# nes_snes_4_port.net
KiCad netlist of a schematic drawn in EAGLE
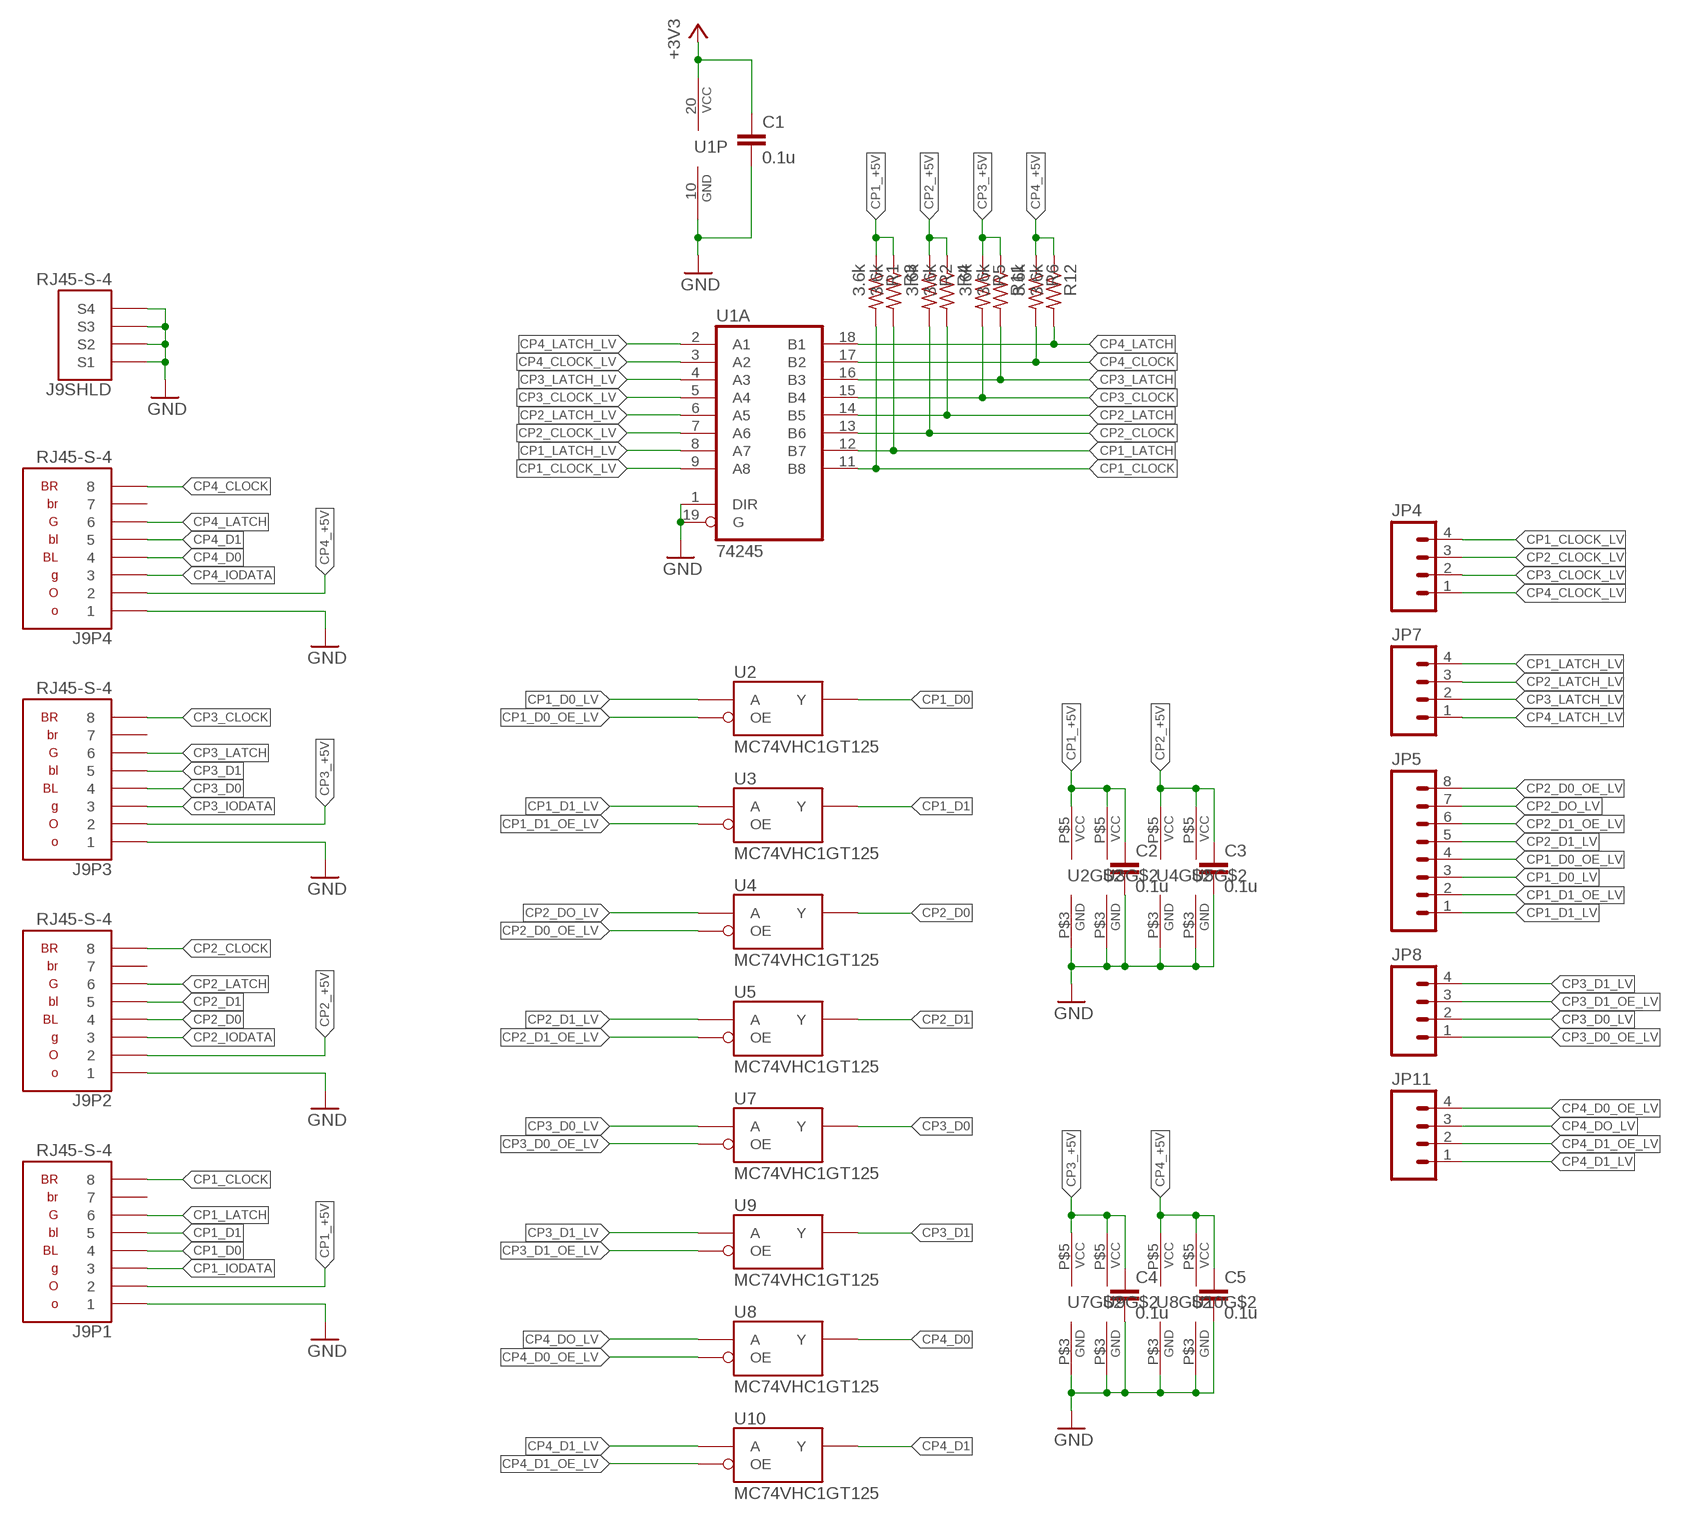
[diagram p0: schematic, sheet 1, part 1 of 2]
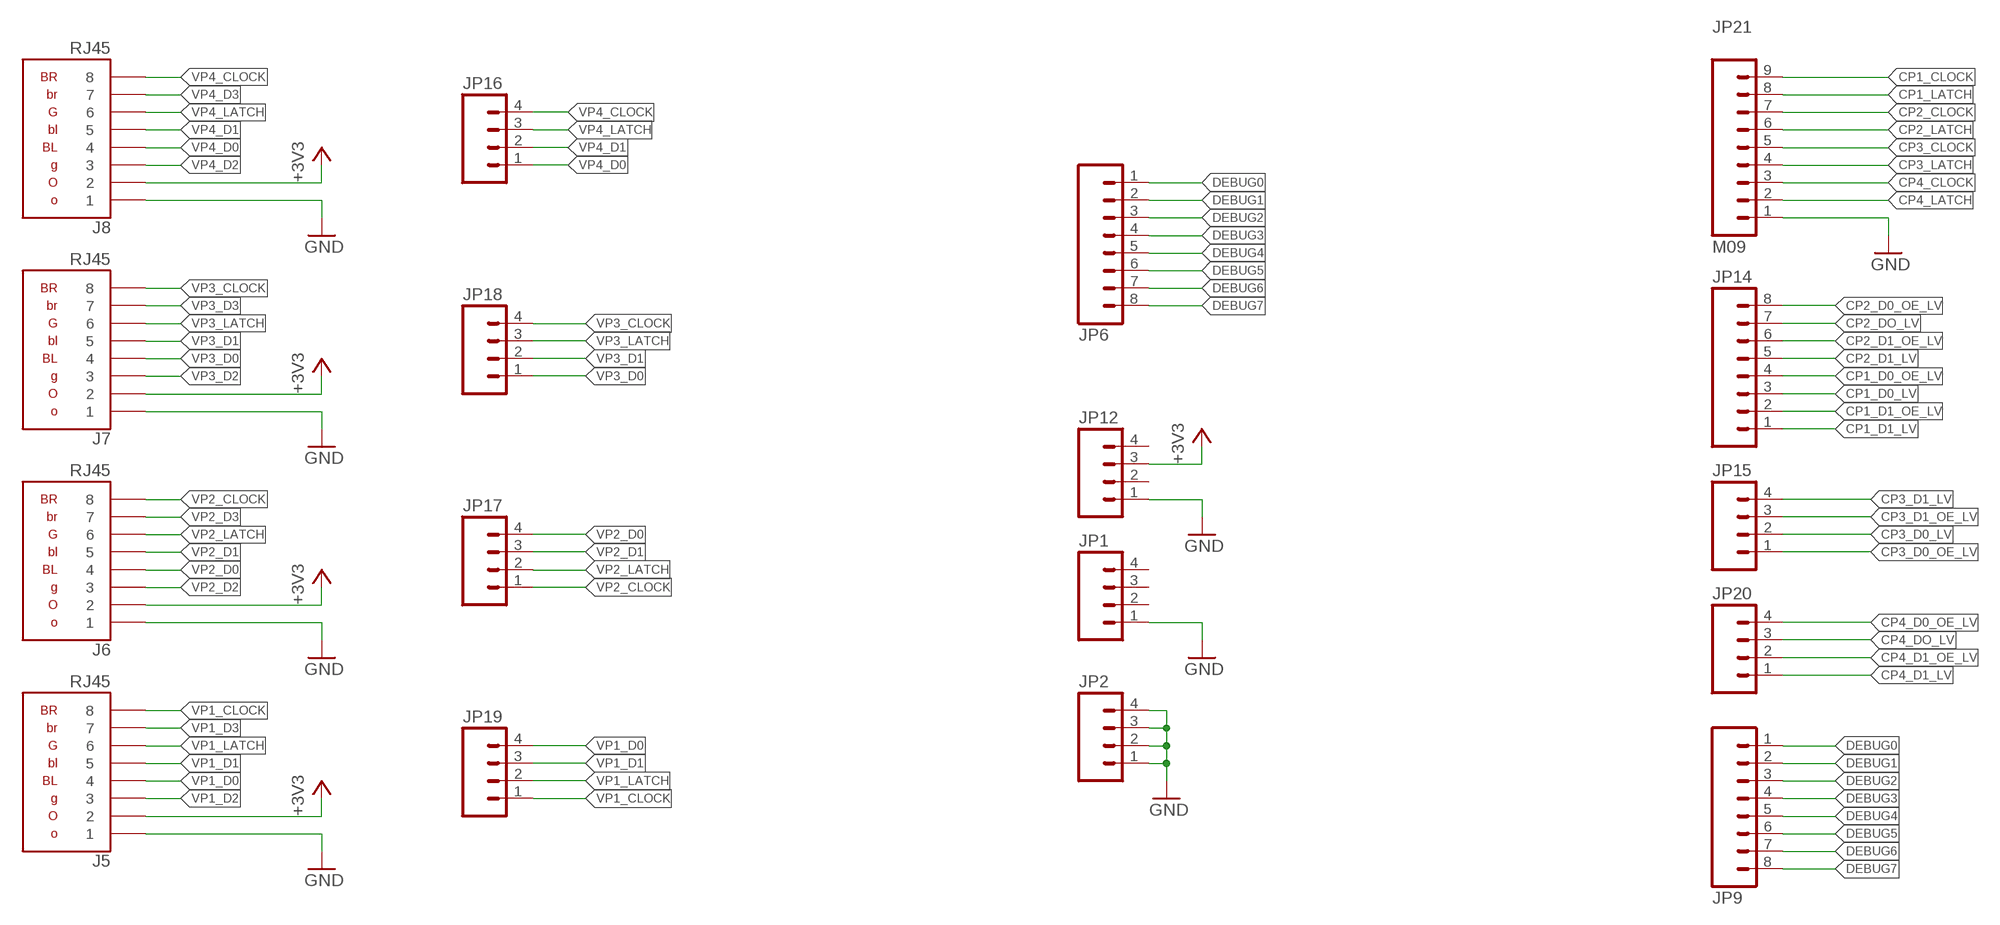
[diagram p1: schematic, sheet 1, part 2 of 2]

(export (version "E")
  (design (tool "Eeschema 10.0.6"))
  (components
    (comp (ref "C1")
      (value "0.1u")
      (footprint "eagle-import:C0603")
      (libsource (lib "eagle-import") (part "C-EUC0603"))
    )
    (comp (ref "C2")
      (value "0.1u")
      (footprint "eagle-import:C0603")
      (libsource (lib "eagle-import") (part "C-EUC0603"))
    )
    (comp (ref "C3")
      (value "0.1u")
      (footprint "eagle-import:C0603")
      (libsource (lib "eagle-import") (part "C-EUC0603"))
    )
    (comp (ref "C4")
      (value "0.1u")
      (footprint "eagle-import:C0603")
      (libsource (lib "eagle-import") (part "C-EUC0603"))
    )
    (comp (ref "C5")
      (value "0.1u")
      (footprint "eagle-import:C0603")
      (libsource (lib "eagle-import") (part "C-EUC0603"))
    )
    (comp (ref "J5")
      (value "RJ45")
      (footprint "eagle-import:RJ45")
      (libsource (lib "eagle-import") (part "RJ45"))
    )
    (comp (ref "J6")
      (value "RJ45")
      (footprint "eagle-import:RJ45")
      (libsource (lib "eagle-import") (part "RJ45"))
    )
    (comp (ref "J7")
      (value "RJ45")
      (footprint "eagle-import:RJ45")
      (libsource (lib "eagle-import") (part "RJ45"))
    )
    (comp (ref "J8")
      (value "RJ45")
      (footprint "eagle-import:RJ45")
      (libsource (lib "eagle-import") (part "RJ45"))
    )
    (comp (ref "J9")
      (value "RJ45-S-4")
      (footprint "eagle-import:RJ45-S-4")
      (libsource (lib "eagle-import") (part "RJ45-S-4"))
    )
    (comp (ref "JP1")
      (value "M04PTH")
      (footprint "eagle-import:1X04")
      (libsource (lib "eagle-import") (part "M04PTH"))
    )
    (comp (ref "JP2")
      (value "M04PTH")
      (footprint "eagle-import:1X04")
      (libsource (lib "eagle-import") (part "M04PTH"))
    )
    (comp (ref "JP4")
      (value "M04PTH")
      (footprint "eagle-import:1X04")
      (libsource (lib "eagle-import") (part "M04PTH"))
    )
    (comp (ref "JP5")
      (value "M081X08")
      (footprint "eagle-import:1X08")
      (libsource (lib "eagle-import") (part "M081X08"))
    )
    (comp (ref "JP6")
      (value "M081X08")
      (footprint "eagle-import:1X08")
      (libsource (lib "eagle-import") (part "M081X08"))
    )
    (comp (ref "JP7")
      (value "M04PTH")
      (footprint "eagle-import:1X04")
      (libsource (lib "eagle-import") (part "M04PTH"))
    )
    (comp (ref "JP8")
      (value "M04PTH")
      (footprint "eagle-import:1X04")
      (libsource (lib "eagle-import") (part "M04PTH"))
    )
    (comp (ref "JP9")
      (value "M081X08")
      (footprint "eagle-import:1X08")
      (libsource (lib "eagle-import") (part "M081X08"))
    )
    (comp (ref "JP11")
      (value "M04PTH")
      (footprint "eagle-import:1X04")
      (libsource (lib "eagle-import") (part "M04PTH"))
    )
    (comp (ref "JP12")
      (value "M04PTH")
      (footprint "eagle-import:1X04")
      (libsource (lib "eagle-import") (part "M04PTH"))
    )
    (comp (ref "JP14")
      (value "M081X08")
      (footprint "eagle-import:1X08")
      (libsource (lib "eagle-import") (part "M081X08"))
    )
    (comp (ref "JP15")
      (value "M04PTH")
      (footprint "eagle-import:1X04")
      (libsource (lib "eagle-import") (part "M04PTH"))
    )
    (comp (ref "JP16")
      (value "M04PTH")
      (footprint "eagle-import:1X04")
      (libsource (lib "eagle-import") (part "M04PTH"))
    )
    (comp (ref "JP17")
      (value "M04PTH")
      (footprint "eagle-import:1X04")
      (libsource (lib "eagle-import") (part "M04PTH"))
    )
    (comp (ref "JP18")
      (value "M04PTH")
      (footprint "eagle-import:1X04")
      (libsource (lib "eagle-import") (part "M04PTH"))
    )
    (comp (ref "JP19")
      (value "M04PTH")
      (footprint "eagle-import:1X04")
      (libsource (lib "eagle-import") (part "M04PTH"))
    )
    (comp (ref "JP20")
      (value "M04PTH")
      (footprint "eagle-import:1X04")
      (libsource (lib "eagle-import") (part "M04PTH"))
    )
    (comp (ref "JP21")
      (value "M09")
      (footprint "eagle-import:1X09")
      (libsource (lib "eagle-import") (part "M09"))
    )
    (comp (ref "R1")
      (value "3.6k")
      (footprint "eagle-import:0207_2V")
      (libsource (lib "eagle-import") (part "R-US_0207/2V"))
    )
    (comp (ref "R2")
      (value "3.6k")
      (footprint "eagle-import:0207_2V")
      (libsource (lib "eagle-import") (part "R-US_0207/2V"))
    )
    (comp (ref "R3")
      (value "3.6k")
      (footprint "eagle-import:0207_2V")
      (libsource (lib "eagle-import") (part "R-US_0207/2V"))
    )
    (comp (ref "R4")
      (value "3.6k")
      (footprint "eagle-import:0207_2V")
      (libsource (lib "eagle-import") (part "R-US_0207/2V"))
    )
    (comp (ref "R5")
      (value "3.6k")
      (footprint "eagle-import:0207_2V")
      (libsource (lib "eagle-import") (part "R-US_0207/2V"))
    )
    (comp (ref "R6")
      (value "3.6k")
      (footprint "eagle-import:0207_2V")
      (libsource (lib "eagle-import") (part "R-US_0207/2V"))
    )
    (comp (ref "R11")
      (value "3.6k")
      (footprint "eagle-import:0207_2V")
      (libsource (lib "eagle-import") (part "R-US_0207/2V"))
    )
    (comp (ref "R12")
      (value "3.6k")
      (footprint "eagle-import:0207_2V")
      (libsource (lib "eagle-import") (part "R-US_0207/2V"))
    )
    (comp (ref "U1")
      (value "74245")
      (footprint "eagle-import:DIL20")
      (libsource (lib "eagle-import") (part "74245"))
    )
    (comp (ref "U2")
      (value "MC74VHC1GT125")
      (footprint "eagle-import:TSOP-5")
      (libsource (lib "eagle-import") (part "MC74VHC1GT125"))
    )
    (comp (ref "U3")
      (value "MC74VHC1GT125")
      (footprint "eagle-import:TSOP-5")
      (libsource (lib "eagle-import") (part "MC74VHC1GT125"))
    )
    (comp (ref "U4")
      (value "MC74VHC1GT125")
      (footprint "eagle-import:TSOP-5")
      (libsource (lib "eagle-import") (part "MC74VHC1GT125"))
    )
    (comp (ref "U5")
      (value "MC74VHC1GT125")
      (footprint "eagle-import:TSOP-5")
      (libsource (lib "eagle-import") (part "MC74VHC1GT125"))
    )
    (comp (ref "U7")
      (value "MC74VHC1GT125")
      (footprint "eagle-import:TSOP-5")
      (libsource (lib "eagle-import") (part "MC74VHC1GT125"))
    )
    (comp (ref "U8")
      (value "MC74VHC1GT125")
      (footprint "eagle-import:TSOP-5")
      (libsource (lib "eagle-import") (part "MC74VHC1GT125"))
    )
    (comp (ref "U9")
      (value "MC74VHC1GT125")
      (footprint "eagle-import:TSOP-5")
      (libsource (lib "eagle-import") (part "MC74VHC1GT125"))
    )
    (comp (ref "U10")
      (value "MC74VHC1GT125")
      (footprint "eagle-import:TSOP-5")
      (libsource (lib "eagle-import") (part "MC74VHC1GT125"))
    )
  )
  (nets
    (net (code "1") (name "+3V3") (class "Default")
      (node (ref "C1") (pin "1") (pinfunction "1_1") (pintype "passive"))
      (node (ref "J5") (pin "2") (pinfunction "2_2") (pintype "bidirectional"))
      (node (ref "J6") (pin "2") (pinfunction "2_2") (pintype "bidirectional"))
      (node (ref "J7") (pin "2") (pinfunction "2_2") (pintype "bidirectional"))
      (node (ref "J8") (pin "2") (pinfunction "2_2") (pintype "bidirectional"))
      (node (ref "JP12") (pin "3") (pinfunction "3_3") (pintype "passive"))
      (node (ref "U1") (pin "20") (pinfunction "VCC_20") (pintype "power_in"))
    )
    (net (code "2") (name "CP1_+5V") (class "Default")
      (node (ref "C2") (pin "1") (pinfunction "1_1") (pintype "passive"))
      (node (ref "J9") (pin "1-2") (pinfunction "2_1-2") (pintype "bidirectional"))
      (node (ref "R1") (pin "1") (pinfunction "1_1") (pintype "passive"))
      (node (ref "R3") (pin "1") (pinfunction "1_1") (pintype "passive"))
      (node (ref "U2") (pin "P$5") (pinfunction "VCC_P$5") (pintype "power_in"))
      (node (ref "U3") (pin "P$5") (pinfunction "VCC_P$5") (pintype "power_in"))
    )
    (net (code "3") (name "CP1_CLOCK") (class "Default")
      (node (ref "J9") (pin "1-8") (pinfunction "8_1-8") (pintype "bidirectional"))
      (node (ref "JP21") (pin "9") (pinfunction "9_9") (pintype "passive"))
      (node (ref "R1") (pin "2") (pinfunction "2_2") (pintype "passive"))
      (node (ref "U1") (pin "11") (pinfunction "B8_11") (pintype "bidirectional"))
    )
    (net (code "4") (name "CP1_CLOCK_LV") (class "Default")
      (node (ref "JP4") (pin "4") (pinfunction "4_4") (pintype "passive"))
      (node (ref "U1") (pin "9") (pinfunction "A8_9") (pintype "bidirectional"))
    )
    (net (code "5") (name "CP1_D0") (class "Default")
      (node (ref "J9") (pin "1-4") (pinfunction "4_1-4") (pintype "bidirectional"))
      (node (ref "U2") (pin "P$4") (pinfunction "Y_P$4") (pintype "bidirectional"))
    )
    (net (code "6") (name "CP1_D0_LV") (class "Default")
      (node (ref "JP14") (pin "3") (pinfunction "3_3") (pintype "passive"))
      (node (ref "JP5") (pin "3") (pinfunction "3_3") (pintype "passive"))
      (node (ref "U2") (pin "P$2") (pinfunction "A_P$2") (pintype "bidirectional"))
    )
    (net (code "7") (name "CP1_D0_OE_LV") (class "Default")
      (node (ref "JP14") (pin "4") (pinfunction "4_4") (pintype "passive"))
      (node (ref "JP5") (pin "4") (pinfunction "4_4") (pintype "passive"))
      (node (ref "U2") (pin "P$1") (pinfunction "OE_P$1") (pintype "bidirectional"))
    )
    (net (code "8") (name "CP1_D1") (class "Default")
      (node (ref "J9") (pin "1-5") (pinfunction "5_1-5") (pintype "bidirectional"))
      (node (ref "U3") (pin "P$4") (pinfunction "Y_P$4") (pintype "bidirectional"))
    )
    (net (code "9") (name "CP1_D1_LV") (class "Default")
      (node (ref "JP14") (pin "1") (pinfunction "1_1") (pintype "passive"))
      (node (ref "JP5") (pin "1") (pinfunction "1_1") (pintype "passive"))
      (node (ref "U3") (pin "P$2") (pinfunction "A_P$2") (pintype "bidirectional"))
    )
    (net (code "10") (name "CP1_D1_OE_LV") (class "Default")
      (node (ref "JP14") (pin "2") (pinfunction "2_2") (pintype "passive"))
      (node (ref "JP5") (pin "2") (pinfunction "2_2") (pintype "passive"))
      (node (ref "U3") (pin "P$1") (pinfunction "OE_P$1") (pintype "bidirectional"))
    )
    (net (code "11") (name "CP1_IODATA") (class "Default")
      (node (ref "J9") (pin "1-3") (pinfunction "3_1-3") (pintype "bidirectional"))
    )
    (net (code "12") (name "CP1_LATCH") (class "Default")
      (node (ref "J9") (pin "1-6") (pinfunction "6_1-6") (pintype "bidirectional"))
      (node (ref "JP21") (pin "8") (pinfunction "8_8") (pintype "passive"))
      (node (ref "R3") (pin "2") (pinfunction "2_2") (pintype "passive"))
      (node (ref "U1") (pin "12") (pinfunction "B7_12") (pintype "bidirectional"))
    )
    (net (code "13") (name "CP1_LATCH_LV") (class "Default")
      (node (ref "JP7") (pin "4") (pinfunction "4_4") (pintype "passive"))
      (node (ref "U1") (pin "8") (pinfunction "A7_8") (pintype "bidirectional"))
    )
    (net (code "14") (name "CP2_+5V") (class "Default")
      (node (ref "C3") (pin "1") (pinfunction "1_1") (pintype "passive"))
      (node (ref "J9") (pin "2-2") (pinfunction "2_2-2") (pintype "bidirectional"))
      (node (ref "R2") (pin "1") (pinfunction "1_1") (pintype "passive"))
      (node (ref "R4") (pin "1") (pinfunction "1_1") (pintype "passive"))
      (node (ref "U4") (pin "P$5") (pinfunction "VCC_P$5") (pintype "power_in"))
      (node (ref "U5") (pin "P$5") (pinfunction "VCC_P$5") (pintype "power_in"))
    )
    (net (code "15") (name "CP2_CLOCK") (class "Default")
      (node (ref "J9") (pin "2-8") (pinfunction "8_2-8") (pintype "bidirectional"))
      (node (ref "JP21") (pin "7") (pinfunction "7_7") (pintype "passive"))
      (node (ref "R2") (pin "2") (pinfunction "2_2") (pintype "passive"))
      (node (ref "U1") (pin "13") (pinfunction "B6_13") (pintype "bidirectional"))
    )
    (net (code "16") (name "CP2_CLOCK_LV") (class "Default")
      (node (ref "JP4") (pin "3") (pinfunction "3_3") (pintype "passive"))
      (node (ref "U1") (pin "7") (pinfunction "A6_7") (pintype "bidirectional"))
    )
    (net (code "17") (name "CP2_D0") (class "Default")
      (node (ref "J9") (pin "2-4") (pinfunction "4_2-4") (pintype "bidirectional"))
      (node (ref "U4") (pin "P$4") (pinfunction "Y_P$4") (pintype "bidirectional"))
    )
    (net (code "18") (name "CP2_D0_OE_LV") (class "Default")
      (node (ref "JP14") (pin "8") (pinfunction "8_8") (pintype "passive"))
      (node (ref "JP5") (pin "8") (pinfunction "8_8") (pintype "passive"))
      (node (ref "U4") (pin "P$1") (pinfunction "OE_P$1") (pintype "bidirectional"))
    )
    (net (code "19") (name "CP2_D1") (class "Default")
      (node (ref "J9") (pin "2-5") (pinfunction "5_2-5") (pintype "bidirectional"))
      (node (ref "U5") (pin "P$4") (pinfunction "Y_P$4") (pintype "bidirectional"))
    )
    (net (code "20") (name "CP2_D1_LV") (class "Default")
      (node (ref "JP14") (pin "5") (pinfunction "5_5") (pintype "passive"))
      (node (ref "JP5") (pin "5") (pinfunction "5_5") (pintype "passive"))
      (node (ref "U5") (pin "P$2") (pinfunction "A_P$2") (pintype "bidirectional"))
    )
    (net (code "21") (name "CP2_D1_OE_LV") (class "Default")
      (node (ref "JP14") (pin "6") (pinfunction "6_6") (pintype "passive"))
      (node (ref "JP5") (pin "6") (pinfunction "6_6") (pintype "passive"))
      (node (ref "U5") (pin "P$1") (pinfunction "OE_P$1") (pintype "bidirectional"))
    )
    (net (code "22") (name "CP2_DO_LV") (class "Default")
      (node (ref "JP14") (pin "7") (pinfunction "7_7") (pintype "passive"))
      (node (ref "JP5") (pin "7") (pinfunction "7_7") (pintype "passive"))
      (node (ref "U4") (pin "P$2") (pinfunction "A_P$2") (pintype "bidirectional"))
    )
    (net (code "23") (name "CP2_IODATA") (class "Default")
      (node (ref "J9") (pin "2-3") (pinfunction "3_2-3") (pintype "bidirectional"))
    )
    (net (code "24") (name "CP2_LATCH") (class "Default")
      (node (ref "J9") (pin "2-6") (pinfunction "6_2-6") (pintype "bidirectional"))
      (node (ref "JP21") (pin "6") (pinfunction "6_6") (pintype "passive"))
      (node (ref "R4") (pin "2") (pinfunction "2_2") (pintype "passive"))
      (node (ref "U1") (pin "14") (pinfunction "B5_14") (pintype "bidirectional"))
    )
    (net (code "25") (name "CP2_LATCH_LV") (class "Default")
      (node (ref "JP7") (pin "3") (pinfunction "3_3") (pintype "passive"))
      (node (ref "U1") (pin "6") (pinfunction "A5_6") (pintype "bidirectional"))
    )
    (net (code "26") (name "CP3_+5V") (class "Default")
      (node (ref "C4") (pin "1") (pinfunction "1_1") (pintype "passive"))
      (node (ref "J9") (pin "3-2") (pinfunction "2_3-2") (pintype "bidirectional"))
      (node (ref "R11") (pin "1") (pinfunction "1_1") (pintype "passive"))
      (node (ref "R5") (pin "1") (pinfunction "1_1") (pintype "passive"))
      (node (ref "U7") (pin "P$5") (pinfunction "VCC_P$5") (pintype "power_in"))
      (node (ref "U9") (pin "P$5") (pinfunction "VCC_P$5") (pintype "power_in"))
    )
    (net (code "27") (name "CP3_CLOCK") (class "Default")
      (node (ref "J9") (pin "3-8") (pinfunction "8_3-8") (pintype "bidirectional"))
      (node (ref "JP21") (pin "5") (pinfunction "5_5") (pintype "passive"))
      (node (ref "R5") (pin "2") (pinfunction "2_2") (pintype "passive"))
      (node (ref "U1") (pin "15") (pinfunction "B4_15") (pintype "bidirectional"))
    )
    (net (code "28") (name "CP3_CLOCK_LV") (class "Default")
      (node (ref "JP4") (pin "2") (pinfunction "2_2") (pintype "passive"))
      (node (ref "U1") (pin "5") (pinfunction "A4_5") (pintype "bidirectional"))
    )
    (net (code "29") (name "CP3_D0") (class "Default")
      (node (ref "J9") (pin "3-4") (pinfunction "4_3-4") (pintype "bidirectional"))
      (node (ref "U7") (pin "P$4") (pinfunction "Y_P$4") (pintype "bidirectional"))
    )
    (net (code "30") (name "CP3_D0_LV") (class "Default")
      (node (ref "JP15") (pin "2") (pinfunction "2_2") (pintype "passive"))
      (node (ref "JP8") (pin "2") (pinfunction "2_2") (pintype "passive"))
      (node (ref "U7") (pin "P$2") (pinfunction "A_P$2") (pintype "bidirectional"))
    )
    (net (code "31") (name "CP3_D0_OE_LV") (class "Default")
      (node (ref "JP15") (pin "1") (pinfunction "1_1") (pintype "passive"))
      (node (ref "JP8") (pin "1") (pinfunction "1_1") (pintype "passive"))
      (node (ref "U7") (pin "P$1") (pinfunction "OE_P$1") (pintype "bidirectional"))
    )
    (net (code "32") (name "CP3_D1") (class "Default")
      (node (ref "J9") (pin "3-5") (pinfunction "5_3-5") (pintype "bidirectional"))
      (node (ref "U9") (pin "P$4") (pinfunction "Y_P$4") (pintype "bidirectional"))
    )
    (net (code "33") (name "CP3_D1_LV") (class "Default")
      (node (ref "JP15") (pin "4") (pinfunction "4_4") (pintype "passive"))
      (node (ref "JP8") (pin "4") (pinfunction "4_4") (pintype "passive"))
      (node (ref "U9") (pin "P$2") (pinfunction "A_P$2") (pintype "bidirectional"))
    )
    (net (code "34") (name "CP3_D1_OE_LV") (class "Default")
      (node (ref "JP15") (pin "3") (pinfunction "3_3") (pintype "passive"))
      (node (ref "JP8") (pin "3") (pinfunction "3_3") (pintype "passive"))
      (node (ref "U9") (pin "P$1") (pinfunction "OE_P$1") (pintype "bidirectional"))
    )
    (net (code "35") (name "CP3_IODATA") (class "Default")
      (node (ref "J9") (pin "3-3") (pinfunction "3_3-3") (pintype "bidirectional"))
    )
    (net (code "36") (name "CP3_LATCH") (class "Default")
      (node (ref "J9") (pin "3-6") (pinfunction "6_3-6") (pintype "bidirectional"))
      (node (ref "JP21") (pin "4") (pinfunction "4_4") (pintype "passive"))
      (node (ref "R11") (pin "2") (pinfunction "2_2") (pintype "passive"))
      (node (ref "U1") (pin "16") (pinfunction "B3_16") (pintype "bidirectional"))
    )
    (net (code "37") (name "CP3_LATCH_LV") (class "Default")
      (node (ref "JP7") (pin "2") (pinfunction "2_2") (pintype "passive"))
      (node (ref "U1") (pin "4") (pinfunction "A3_4") (pintype "bidirectional"))
    )
    (net (code "38") (name "CP4_+5V") (class "Default")
      (node (ref "C5") (pin "1") (pinfunction "1_1") (pintype "passive"))
      (node (ref "J9") (pin "4-2") (pinfunction "2_4-2") (pintype "bidirectional"))
      (node (ref "R12") (pin "1") (pinfunction "1_1") (pintype "passive"))
      (node (ref "R6") (pin "1") (pinfunction "1_1") (pintype "passive"))
      (node (ref "U10") (pin "P$5") (pinfunction "VCC_P$5") (pintype "power_in"))
      (node (ref "U8") (pin "P$5") (pinfunction "VCC_P$5") (pintype "power_in"))
    )
    (net (code "39") (name "CP4_CLOCK") (class "Default")
      (node (ref "J9") (pin "4-8") (pinfunction "8_4-8") (pintype "bidirectional"))
      (node (ref "JP21") (pin "3") (pinfunction "3_3") (pintype "passive"))
      (node (ref "R6") (pin "2") (pinfunction "2_2") (pintype "passive"))
      (node (ref "U1") (pin "17") (pinfunction "B2_17") (pintype "bidirectional"))
    )
    (net (code "40") (name "CP4_CLOCK_LV") (class "Default")
      (node (ref "JP4") (pin "1") (pinfunction "1_1") (pintype "passive"))
      (node (ref "U1") (pin "3") (pinfunction "A2_3") (pintype "bidirectional"))
    )
    (net (code "41") (name "CP4_D0") (class "Default")
      (node (ref "J9") (pin "4-4") (pinfunction "4_4-4") (pintype "bidirectional"))
      (node (ref "U8") (pin "P$4") (pinfunction "Y_P$4") (pintype "bidirectional"))
    )
    (net (code "42") (name "CP4_D0_OE_LV") (class "Default")
      (node (ref "JP11") (pin "4") (pinfunction "4_4") (pintype "passive"))
      (node (ref "JP20") (pin "4") (pinfunction "4_4") (pintype "passive"))
      (node (ref "U8") (pin "P$1") (pinfunction "OE_P$1") (pintype "bidirectional"))
    )
    (net (code "43") (name "CP4_D1") (class "Default")
      (node (ref "J9") (pin "4-5") (pinfunction "5_4-5") (pintype "bidirectional"))
      (node (ref "U10") (pin "P$4") (pinfunction "Y_P$4") (pintype "bidirectional"))
    )
    (net (code "44") (name "CP4_D1_LV") (class "Default")
      (node (ref "JP11") (pin "1") (pinfunction "1_1") (pintype "passive"))
      (node (ref "JP20") (pin "1") (pinfunction "1_1") (pintype "passive"))
      (node (ref "U10") (pin "P$2") (pinfunction "A_P$2") (pintype "bidirectional"))
    )
    (net (code "45") (name "CP4_D1_OE_LV") (class "Default")
      (node (ref "JP11") (pin "2") (pinfunction "2_2") (pintype "passive"))
      (node (ref "JP20") (pin "2") (pinfunction "2_2") (pintype "passive"))
      (node (ref "U10") (pin "P$1") (pinfunction "OE_P$1") (pintype "bidirectional"))
    )
    (net (code "46") (name "CP4_DO_LV") (class "Default")
      (node (ref "JP11") (pin "3") (pinfunction "3_3") (pintype "passive"))
      (node (ref "JP20") (pin "3") (pinfunction "3_3") (pintype "passive"))
      (node (ref "U8") (pin "P$2") (pinfunction "A_P$2") (pintype "bidirectional"))
    )
    (net (code "47") (name "CP4_IODATA") (class "Default")
      (node (ref "J9") (pin "4-3") (pinfunction "3_4-3") (pintype "bidirectional"))
    )
    (net (code "48") (name "CP4_LATCH") (class "Default")
      (node (ref "J9") (pin "4-6") (pinfunction "6_4-6") (pintype "bidirectional"))
      (node (ref "JP21") (pin "2") (pinfunction "2_2") (pintype "passive"))
      (node (ref "R12") (pin "2") (pinfunction "2_2") (pintype "passive"))
      (node (ref "U1") (pin "18") (pinfunction "B1_18") (pintype "bidirectional"))
    )
    (net (code "49") (name "CP4_LATCH_LV") (class "Default")
      (node (ref "JP7") (pin "1") (pinfunction "1_1") (pintype "passive"))
      (node (ref "U1") (pin "2") (pinfunction "A1_2") (pintype "bidirectional"))
    )
    (net (code "50") (name "DEBUG0") (class "Default")
      (node (ref "JP6") (pin "1") (pinfunction "1_1") (pintype "passive"))
      (node (ref "JP9") (pin "1") (pinfunction "1_1") (pintype "passive"))
    )
    (net (code "51") (name "DEBUG1") (class "Default")
      (node (ref "JP6") (pin "2") (pinfunction "2_2") (pintype "passive"))
      (node (ref "JP9") (pin "2") (pinfunction "2_2") (pintype "passive"))
    )
    (net (code "52") (name "DEBUG2") (class "Default")
      (node (ref "JP6") (pin "3") (pinfunction "3_3") (pintype "passive"))
      (node (ref "JP9") (pin "3") (pinfunction "3_3") (pintype "passive"))
    )
    (net (code "53") (name "DEBUG3") (class "Default")
      (node (ref "JP6") (pin "4") (pinfunction "4_4") (pintype "passive"))
      (node (ref "JP9") (pin "4") (pinfunction "4_4") (pintype "passive"))
    )
    (net (code "54") (name "DEBUG4") (class "Default")
      (node (ref "JP6") (pin "5") (pinfunction "5_5") (pintype "passive"))
      (node (ref "JP9") (pin "5") (pinfunction "5_5") (pintype "passive"))
    )
    (net (code "55") (name "DEBUG5") (class "Default")
      (node (ref "JP6") (pin "6") (pinfunction "6_6") (pintype "passive"))
      (node (ref "JP9") (pin "6") (pinfunction "6_6") (pintype "passive"))
    )
    (net (code "56") (name "DEBUG6") (class "Default")
      (node (ref "JP6") (pin "7") (pinfunction "7_7") (pintype "passive"))
      (node (ref "JP9") (pin "7") (pinfunction "7_7") (pintype "passive"))
    )
    (net (code "57") (name "DEBUG7") (class "Default")
      (node (ref "JP6") (pin "8") (pinfunction "8_8") (pintype "passive"))
      (node (ref "JP9") (pin "8") (pinfunction "8_8") (pintype "passive"))
    )
    (net (code "58") (name "GND") (class "Default")
      (node (ref "C1") (pin "2") (pinfunction "2_2") (pintype "passive"))
      (node (ref "C2") (pin "2") (pinfunction "2_2") (pintype "passive"))
      (node (ref "C3") (pin "2") (pinfunction "2_2") (pintype "passive"))
      (node (ref "C4") (pin "2") (pinfunction "2_2") (pintype "passive"))
      (node (ref "C5") (pin "2") (pinfunction "2_2") (pintype "passive"))
      (node (ref "J5") (pin "1") (pinfunction "1_1") (pintype "bidirectional"))
      (node (ref "J6") (pin "1") (pinfunction "1_1") (pintype "bidirectional"))
      (node (ref "J7") (pin "1") (pinfunction "1_1") (pintype "bidirectional"))
      (node (ref "J8") (pin "1") (pinfunction "1_1") (pintype "bidirectional"))
      (node (ref "J9") (pin "1-1") (pinfunction "1_1-1") (pintype "bidirectional"))
      (node (ref "J9") (pin "2-1") (pinfunction "1_2-1") (pintype "bidirectional"))
      (node (ref "J9") (pin "3-1") (pinfunction "1_3-1") (pintype "bidirectional"))
      (node (ref "J9") (pin "4-1") (pinfunction "1_4-1") (pintype "bidirectional"))
      (node (ref "J9") (pin "S1") (pinfunction "S1_S1") (pintype "bidirectional"))
      (node (ref "J9") (pin "S2") (pinfunction "S2_S2") (pintype "bidirectional"))
      (node (ref "J9") (pin "S3") (pinfunction "S3_S3") (pintype "bidirectional"))
      (node (ref "J9") (pin "S4") (pinfunction "S4_S4") (pintype "bidirectional"))
      (node (ref "JP1") (pin "1") (pinfunction "1_1") (pintype "passive"))
      (node (ref "JP12") (pin "1") (pinfunction "1_1") (pintype "passive"))
      (node (ref "JP2") (pin "1") (pinfunction "1_1") (pintype "passive"))
      (node (ref "JP2") (pin "2") (pinfunction "2_2") (pintype "passive"))
      (node (ref "JP2") (pin "3") (pinfunction "3_3") (pintype "passive"))
      (node (ref "JP2") (pin "4") (pinfunction "4_4") (pintype "passive"))
      (node (ref "JP21") (pin "1") (pinfunction "1_1") (pintype "passive"))
      (node (ref "U1") (pin "1") (pinfunction "DIR_1") (pintype "input"))
      (node (ref "U1") (pin "10") (pinfunction "GND_10") (pintype "power_in"))
      (node (ref "U1") (pin "19") (pinfunction "G_19") (pintype "input"))
      (node (ref "U10") (pin "P$3") (pinfunction "GND_P$3") (pintype "power_in"))
      (node (ref "U2") (pin "P$3") (pinfunction "GND_P$3") (pintype "power_in"))
      (node (ref "U3") (pin "P$3") (pinfunction "GND_P$3") (pintype "power_in"))
      (node (ref "U4") (pin "P$3") (pinfunction "GND_P$3") (pintype "power_in"))
      (node (ref "U5") (pin "P$3") (pinfunction "GND_P$3") (pintype "power_in"))
      (node (ref "U7") (pin "P$3") (pinfunction "GND_P$3") (pintype "power_in"))
      (node (ref "U8") (pin "P$3") (pinfunction "GND_P$3") (pintype "power_in"))
      (node (ref "U9") (pin "P$3") (pinfunction "GND_P$3") (pintype "power_in"))
    )
    (net (code "59") (name "VP1_CLOCK") (class "Default")
      (node (ref "J5") (pin "8") (pinfunction "8_8") (pintype "bidirectional"))
      (node (ref "JP19") (pin "1") (pinfunction "1_1") (pintype "passive"))
    )
    (net (code "60") (name "VP1_D0") (class "Default")
      (node (ref "J5") (pin "4") (pinfunction "4_4") (pintype "bidirectional"))
      (node (ref "JP19") (pin "4") (pinfunction "4_4") (pintype "passive"))
    )
    (net (code "61") (name "VP1_D1") (class "Default")
      (node (ref "J5") (pin "5") (pinfunction "5_5") (pintype "bidirectional"))
      (node (ref "JP19") (pin "3") (pinfunction "3_3") (pintype "passive"))
    )
    (net (code "62") (name "VP1_D2") (class "Default")
      (node (ref "J5") (pin "3") (pinfunction "3_3") (pintype "bidirectional"))
    )
    (net (code "63") (name "VP1_D3") (class "Default")
      (node (ref "J5") (pin "7") (pinfunction "7_7") (pintype "bidirectional"))
    )
    (net (code "64") (name "VP1_LATCH") (class "Default")
      (node (ref "J5") (pin "6") (pinfunction "6_6") (pintype "bidirectional"))
      (node (ref "JP19") (pin "2") (pinfunction "2_2") (pintype "passive"))
    )
    (net (code "65") (name "VP2_CLOCK") (class "Default")
      (node (ref "J6") (pin "8") (pinfunction "8_8") (pintype "bidirectional"))
      (node (ref "JP17") (pin "1") (pinfunction "1_1") (pintype "passive"))
    )
    (net (code "66") (name "VP2_D0") (class "Default")
      (node (ref "J6") (pin "4") (pinfunction "4_4") (pintype "bidirectional"))
      (node (ref "JP17") (pin "4") (pinfunction "4_4") (pintype "passive"))
    )
    (net (code "67") (name "VP2_D1") (class "Default")
      (node (ref "J6") (pin "5") (pinfunction "5_5") (pintype "bidirectional"))
      (node (ref "JP17") (pin "3") (pinfunction "3_3") (pintype "passive"))
    )
    (net (code "68") (name "VP2_D2") (class "Default")
      (node (ref "J6") (pin "3") (pinfunction "3_3") (pintype "bidirectional"))
    )
    (net (code "69") (name "VP2_D3") (class "Default")
      (node (ref "J6") (pin "7") (pinfunction "7_7") (pintype "bidirectional"))
    )
    (net (code "70") (name "VP2_LATCH") (class "Default")
      (node (ref "J6") (pin "6") (pinfunction "6_6") (pintype "bidirectional"))
      (node (ref "JP17") (pin "2") (pinfunction "2_2") (pintype "passive"))
    )
    (net (code "71") (name "VP3_CLOCK") (class "Default")
      (node (ref "J7") (pin "8") (pinfunction "8_8") (pintype "bidirectional"))
      (node (ref "JP18") (pin "4") (pinfunction "4_4") (pintype "passive"))
    )
    (net (code "72") (name "VP3_D0") (class "Default")
      (node (ref "J7") (pin "4") (pinfunction "4_4") (pintype "bidirectional"))
      (node (ref "JP18") (pin "1") (pinfunction "1_1") (pintype "passive"))
    )
    (net (code "73") (name "VP3_D1") (class "Default")
      (node (ref "J7") (pin "5") (pinfunction "5_5") (pintype "bidirectional"))
      (node (ref "JP18") (pin "2") (pinfunction "2_2") (pintype "passive"))
    )
    (net (code "74") (name "VP3_D2") (class "Default")
      (node (ref "J7") (pin "3") (pinfunction "3_3") (pintype "bidirectional"))
    )
    (net (code "75") (name "VP3_D3") (class "Default")
      (node (ref "J7") (pin "7") (pinfunction "7_7") (pintype "bidirectional"))
    )
    (net (code "76") (name "VP3_LATCH") (class "Default")
      (node (ref "J7") (pin "6") (pinfunction "6_6") (pintype "bidirectional"))
      (node (ref "JP18") (pin "3") (pinfunction "3_3") (pintype "passive"))
    )
    (net (code "77") (name "VP4_CLOCK") (class "Default")
      (node (ref "J8") (pin "8") (pinfunction "8_8") (pintype "bidirectional"))
      (node (ref "JP16") (pin "4") (pinfunction "4_4") (pintype "passive"))
    )
    (net (code "78") (name "VP4_D0") (class "Default")
      (node (ref "J8") (pin "4") (pinfunction "4_4") (pintype "bidirectional"))
      (node (ref "JP16") (pin "1") (pinfunction "1_1") (pintype "passive"))
    )
    (net (code "79") (name "VP4_D1") (class "Default")
      (node (ref "J8") (pin "5") (pinfunction "5_5") (pintype "bidirectional"))
      (node (ref "JP16") (pin "2") (pinfunction "2_2") (pintype "passive"))
    )
    (net (code "80") (name "VP4_D2") (class "Default")
      (node (ref "J8") (pin "3") (pinfunction "3_3") (pintype "bidirectional"))
    )
    (net (code "81") (name "VP4_D3") (class "Default")
      (node (ref "J8") (pin "7") (pinfunction "7_7") (pintype "bidirectional"))
    )
    (net (code "82") (name "VP4_LATCH") (class "Default")
      (node (ref "J8") (pin "6") (pinfunction "6_6") (pintype "bidirectional"))
      (node (ref "JP16") (pin "3") (pinfunction "3_3") (pintype "passive"))
    )
    (net (code "83") (name "unconnected-(J9A-7-Pad1-7)") (class "Default")
      (node (ref "J9") (pin "1-7") (pinfunction "7_1-7") (pintype "bidirectional"))
    )
    (net (code "84") (name "unconnected-(J9B-7-Pad2-7)") (class "Default")
      (node (ref "J9") (pin "2-7") (pinfunction "7_2-7") (pintype "bidirectional"))
    )
    (net (code "85") (name "unconnected-(J9C-7-Pad3-7)") (class "Default")
      (node (ref "J9") (pin "3-7") (pinfunction "7_3-7") (pintype "bidirectional"))
    )
    (net (code "86") (name "unconnected-(J9D-7-Pad4-7)") (class "Default")
      (node (ref "J9") (pin "4-7") (pinfunction "7_4-7") (pintype "bidirectional"))
    )
    (net (code "87") (name "unconnected-(JP1-Pad2)") (class "Default")
      (node (ref "JP1") (pin "2") (pinfunction "2_2") (pintype "passive"))
    )
    (net (code "88") (name "unconnected-(JP1-Pad3)") (class "Default")
      (node (ref "JP1") (pin "3") (pinfunction "3_3") (pintype "passive"))
    )
    (net (code "89") (name "unconnected-(JP1-Pad4)") (class "Default")
      (node (ref "JP1") (pin "4") (pinfunction "4_4") (pintype "passive"))
    )
    (net (code "90") (name "unconnected-(JP12-Pad2)") (class "Default")
      (node (ref "JP12") (pin "2") (pinfunction "2_2") (pintype "passive"))
    )
    (net (code "91") (name "unconnected-(JP12-Pad4)") (class "Default")
      (node (ref "JP12") (pin "4") (pinfunction "4_4") (pintype "passive"))
    )
  )
)
